# testCircuit.net
KiCad netlist of a schematic drawn in EAGLE
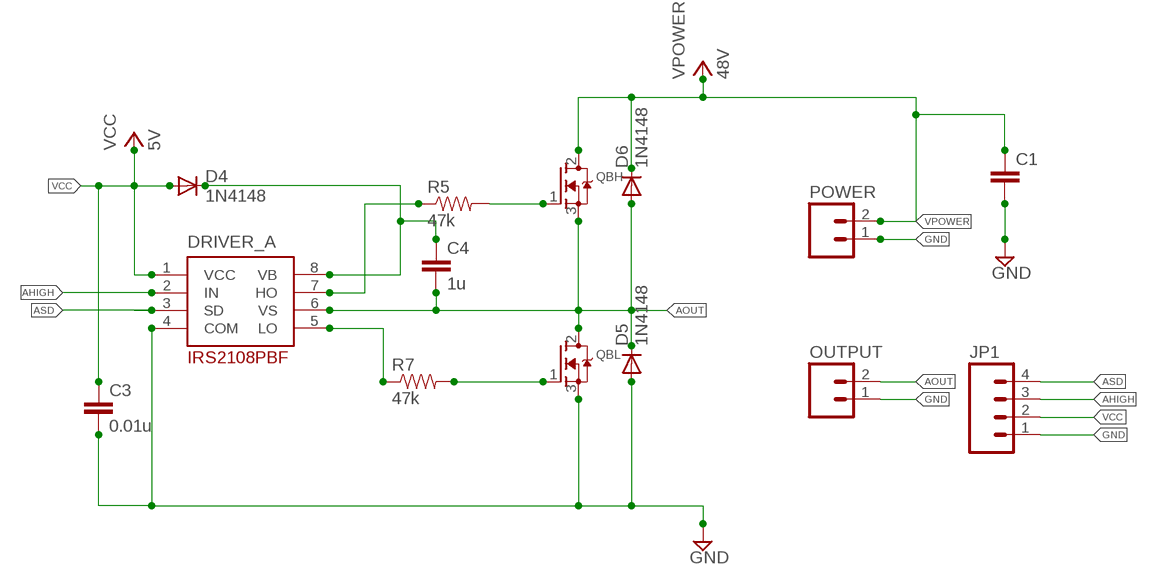
[diagram p0: schematic, sheet 1]

(export (version "E")
  (design (tool "Eeschema 10.0.6"))
  (components
    (comp (ref "C1")
      (value "CAPPTH1")
      (footprint "eagle-import:CAP-PTH-5MM")
      (libsource (lib "eagle-import") (part "CAPPTH1"))
    )
    (comp (ref "C3")
      (value "0.01u")
      (footprint "eagle-import:CAP-PTH-5MM")
      (libsource (lib "eagle-import") (part "CAPPTH1"))
    )
    (comp (ref "C4")
      (value "1u")
      (footprint "eagle-import:CAP-PTH-5MM")
      (libsource (lib "eagle-import") (part "CAPPTH1"))
    )
    (comp (ref "D4")
      (value "1N4148")
      (footprint "eagle-import:DIODE-1N4001")
      (libsource (lib "eagle-import") (part "DIODEPTH"))
    )
    (comp (ref "D5")
      (value "1N4148")
      (footprint "eagle-import:DIODE-1N4001")
      (libsource (lib "eagle-import") (part "DIODEPTH"))
    )
    (comp (ref "D6")
      (value "1N4148")
      (footprint "eagle-import:DIODE-1N4001")
      (libsource (lib "eagle-import") (part "DIODEPTH"))
    )
    (comp (ref "DRIVER_A")
      (value "IRS2108PBF")
      (footprint "eagle-import:DIL08")
      (libsource (lib "eagle-import") (part "IRS2108PBF"))
    )
    (comp (ref "JP1")
      (value "M04LONGPADS")
      (footprint "eagle-import:1X04_LONGPADS")
      (libsource (lib "eagle-import") (part "M04LONGPADS"))
    )
    (comp (ref "OUTPUT")
      (value "TBLOCK-2")
      (footprint "eagle-import:TBLOCK-2")
      (libsource (lib "eagle-import") (part "TBLOCK-2"))
    )
    (comp (ref "POWER")
      (value "TBLOCK-2")
      (footprint "eagle-import:TBLOCK-2")
      (libsource (lib "eagle-import") (part "TBLOCK-2"))
    )
    (comp (ref "QBH")
      (value "MOSFET-NGDS_TO220V")
      (footprint "eagle-import:TO220V")
      (libsource (lib "eagle-import") (part "MOSFET-NGDS_TO220V"))
    )
    (comp (ref "QBL")
      (value "MOSFET-NGDS_TO220V")
      (footprint "eagle-import:TO220V")
      (libsource (lib "eagle-import") (part "MOSFET-NGDS_TO220V"))
    )
    (comp (ref "R5")
      (value "47k")
      (footprint "eagle-import:AXIAL-0.3")
      (libsource (lib "eagle-import") (part "RESISTORAXIAL-0.3"))
    )
    (comp (ref "R7")
      (value "47k")
      (footprint "eagle-import:AXIAL-0.3")
      (libsource (lib "eagle-import") (part "RESISTORAXIAL-0.3"))
    )
  )
  (nets
    (net (code "1") (name "AHIGH") (class "Default")
      (node (ref "DRIVER_A") (pin "2") (pinfunction "IN_2") (pintype "input"))
      (node (ref "JP1") (pin "3") (pinfunction "3_3") (pintype "passive"))
    )
    (net (code "2") (name "AOUT") (class "Default")
      (node (ref "C4") (pin "2") (pinfunction "2_2") (pintype "passive"))
      (node (ref "D5") (pin "C") (pinfunction "C_C") (pintype "passive"))
      (node (ref "D6") (pin "A") (pinfunction "A_A") (pintype "passive"))
      (node (ref "DRIVER_A") (pin "6") (pinfunction "VS_6") (pintype "power_in"))
      (node (ref "OUTPUT") (pin "2") (pinfunction "2_2") (pintype "passive"))
      (node (ref "QBH") (pin "3") (pinfunction "S_3") (pintype "bidirectional"))
      (node (ref "QBL") (pin "2") (pinfunction "D_2") (pintype "bidirectional"))
    )
    (net (code "3") (name "ASD") (class "Default")
      (node (ref "DRIVER_A") (pin "3") (pinfunction "SD_3") (pintype "input"))
      (node (ref "JP1") (pin "4") (pinfunction "4_4") (pintype "passive"))
    )
    (net (code "4") (name "GND") (class "Default")
      (node (ref "C1") (pin "2") (pinfunction "2_2") (pintype "passive"))
      (node (ref "C3") (pin "2") (pinfunction "2_2") (pintype "passive"))
      (node (ref "D5") (pin "A") (pinfunction "A_A") (pintype "passive"))
      (node (ref "DRIVER_A") (pin "4") (pinfunction "COM_4") (pintype "input"))
      (node (ref "JP1") (pin "1") (pinfunction "1_1") (pintype "passive"))
      (node (ref "OUTPUT") (pin "1") (pinfunction "1_1") (pintype "passive"))
      (node (ref "POWER") (pin "1") (pinfunction "1_1") (pintype "passive"))
      (node (ref "QBL") (pin "3") (pinfunction "S_3") (pintype "bidirectional"))
    )
    (net (code "5") (name "Net-(DRIVER_A-HO)") (class "Default")
      (node (ref "DRIVER_A") (pin "7") (pinfunction "HO_7") (pintype "power_in"))
      (node (ref "R5") (pin "P$1") (pinfunction "1_P$1") (pintype "passive"))
    )
    (net (code "6") (name "Net-(DRIVER_A-LO)") (class "Default")
      (node (ref "DRIVER_A") (pin "5") (pinfunction "LO_5") (pintype "power_in"))
      (node (ref "R7") (pin "P$1") (pinfunction "1_P$1") (pintype "passive"))
    )
    (net (code "7") (name "Net-(DRIVER_A-VB)") (class "Default")
      (node (ref "C4") (pin "1") (pinfunction "1_1") (pintype "passive"))
      (node (ref "D4") (pin "C") (pinfunction "C_C") (pintype "passive"))
      (node (ref "DRIVER_A") (pin "8") (pinfunction "VB_8") (pintype "power_in"))
    )
    (net (code "8") (name "Net-(QBH-G)") (class "Default")
      (node (ref "QBH") (pin "1") (pinfunction "G_1") (pintype "bidirectional"))
      (node (ref "R5") (pin "P$2") (pinfunction "2_P$2") (pintype "passive"))
    )
    (net (code "9") (name "Net-(QBL-G)") (class "Default")
      (node (ref "QBL") (pin "1") (pinfunction "G_1") (pintype "bidirectional"))
      (node (ref "R7") (pin "P$2") (pinfunction "2_P$2") (pintype "passive"))
    )
    (net (code "10") (name "VCC") (class "Default")
      (node (ref "C3") (pin "1") (pinfunction "1_1") (pintype "passive"))
      (node (ref "D4") (pin "A") (pinfunction "A_A") (pintype "passive"))
      (node (ref "DRIVER_A") (pin "1") (pinfunction "VCC_1") (pintype "power_in"))
      (node (ref "JP1") (pin "2") (pinfunction "2_2") (pintype "passive"))
    )
    (net (code "11") (name "VPOWER") (class "Default")
      (node (ref "C1") (pin "1") (pinfunction "1_1") (pintype "passive"))
      (node (ref "D6") (pin "C") (pinfunction "C_C") (pintype "passive"))
      (node (ref "POWER") (pin "2") (pinfunction "2_2") (pintype "passive"))
      (node (ref "QBH") (pin "2") (pinfunction "D_2") (pintype "bidirectional"))
    )
  )
)
